# mapleCUx_med_018.net
KiCad netlist of a schematic drawn in EAGLE
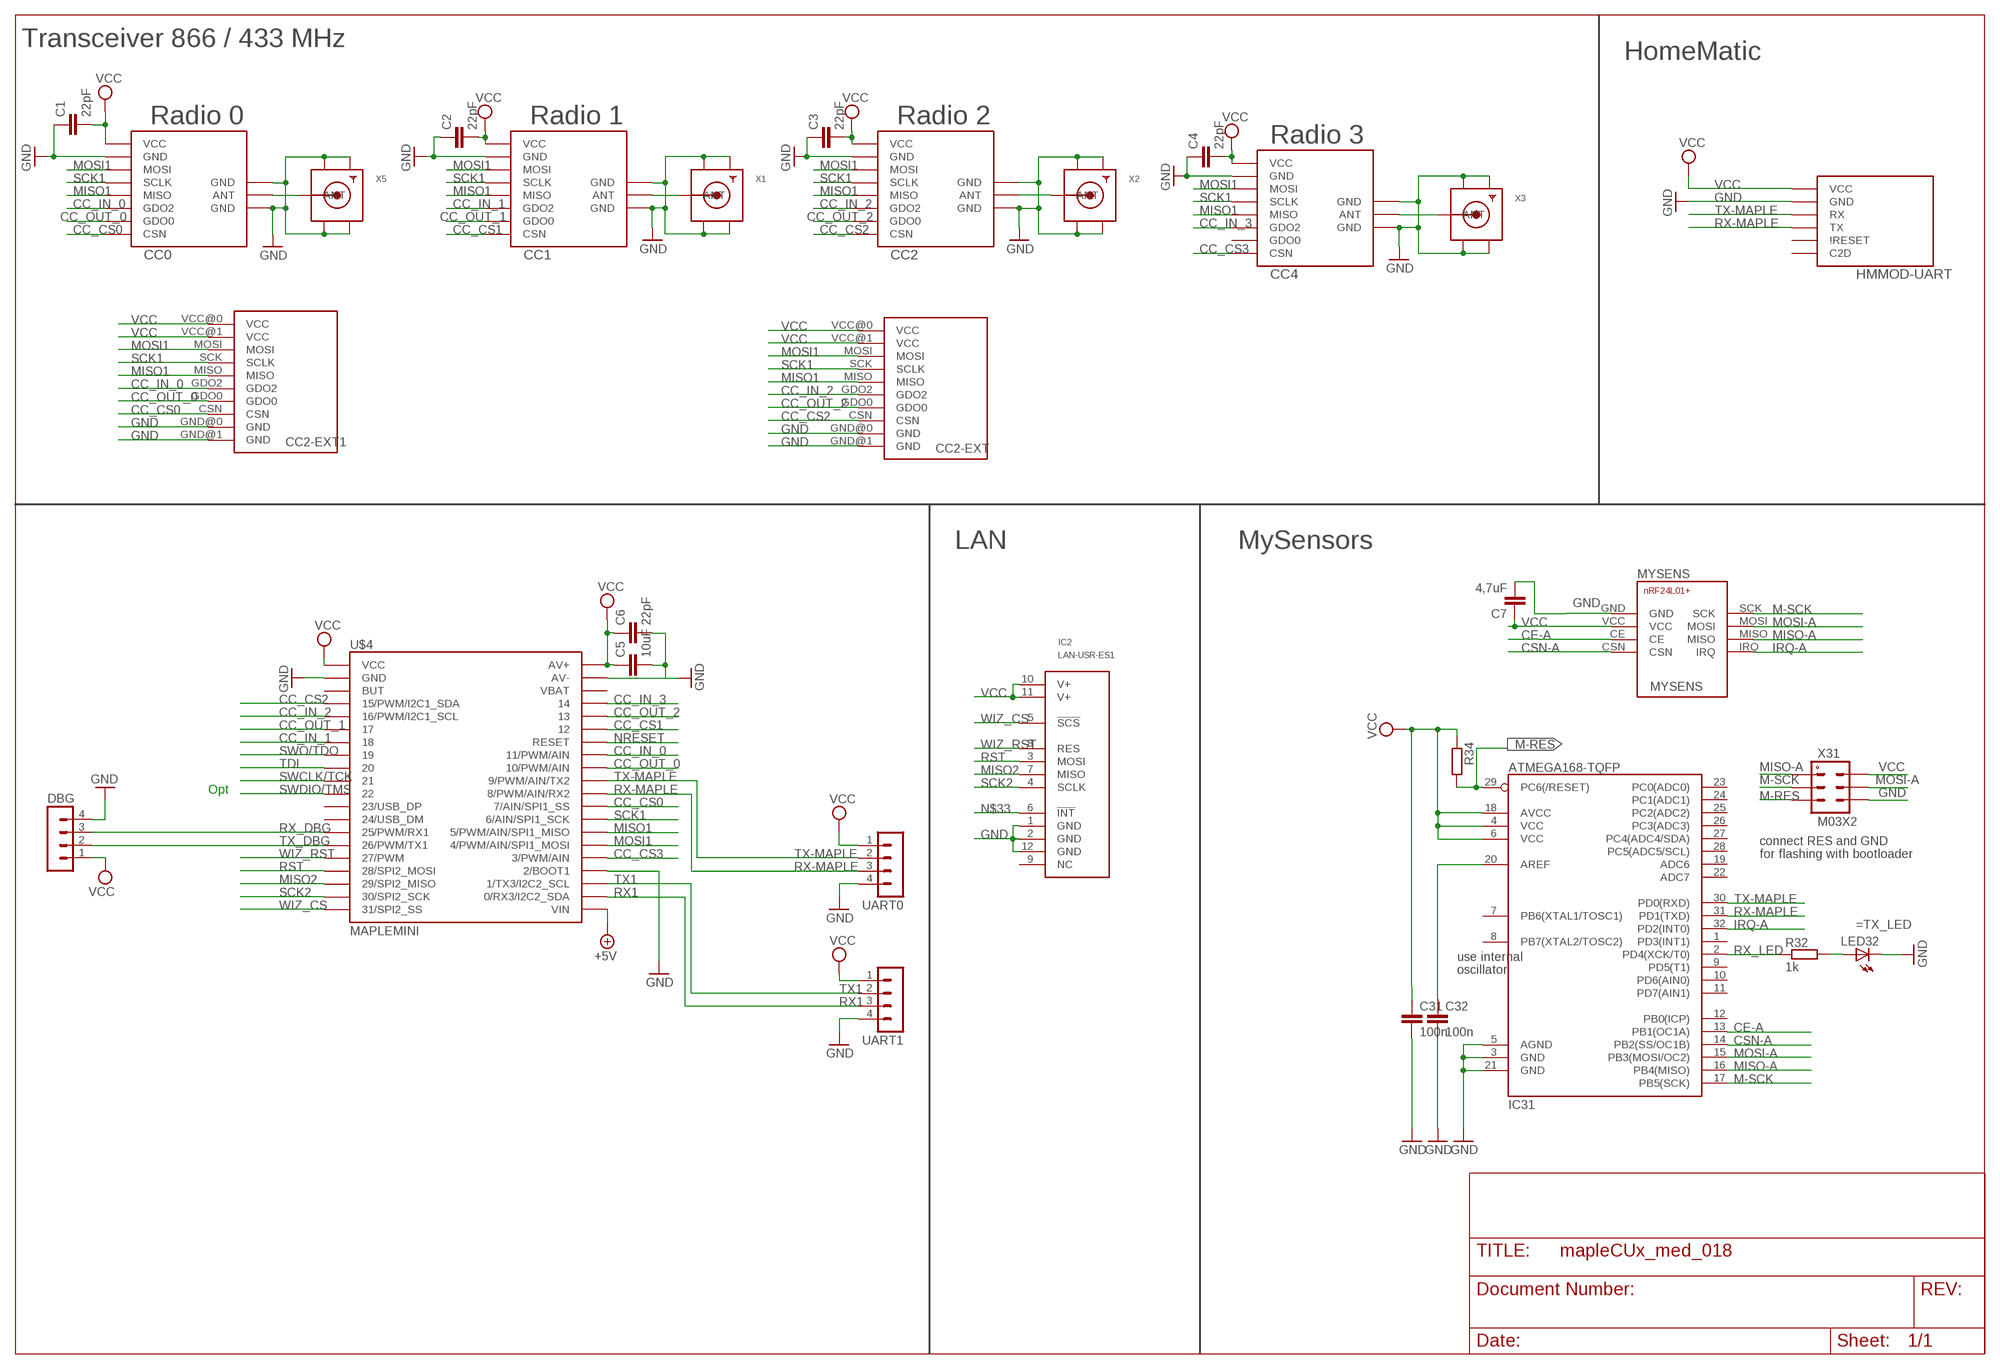
[diagram p0: schematic, sheet 1]

(export (version "E")
  (design (tool "Eeschema 10.0.6"))
  (components
    (comp (ref "C1")
      (value "22pF")
      (footprint "eagle-import:C0805")
      (libsource (lib "eagle-import") (part "C-EUC0805"))
    )
    (comp (ref "C2")
      (value "22pF")
      (footprint "eagle-import:C0805")
      (libsource (lib "eagle-import") (part "C-EUC0805"))
    )
    (comp (ref "C3")
      (value "22pF")
      (footprint "eagle-import:C0805")
      (libsource (lib "eagle-import") (part "C-EUC0805"))
    )
    (comp (ref "C4")
      (value "22pF")
      (footprint "eagle-import:C0805")
      (libsource (lib "eagle-import") (part "C-EUC0805"))
    )
    (comp (ref "C5")
      (value "10uF")
      (footprint "eagle-import:C1210")
      (libsource (lib "eagle-import") (part "C-EUC1210"))
    )
    (comp (ref "C6")
      (value "22pF")
      (footprint "eagle-import:C0805")
      (libsource (lib "eagle-import") (part "C-EUC0805"))
    )
    (comp (ref "C7")
      (value "4,7uF")
      (footprint "eagle-import:C1210")
      (libsource (lib "eagle-import") (part "C-EUC1210"))
    )
    (comp (ref "C31")
      (value "100n")
      (footprint "eagle-import:C0805")
      (libsource (lib "eagle-import") (part "C-EUC0805"))
    )
    (comp (ref "C32")
      (value "100n")
      (footprint "eagle-import:C0805")
      (libsource (lib "eagle-import") (part "C-EUC0805"))
    )
    (comp (ref "CC0")
      (value "CC1101")
      (footprint "eagle-import:CC1101_MODULE1_SMD")
      (libsource (lib "eagle-import") (part "CC1101_MODULE1SMD"))
    )
    (comp (ref "CC1")
      (value "CC1101_MODULE1SMD")
      (footprint "eagle-import:CC1101_MODULE1_SMD")
      (libsource (lib "eagle-import") (part "CC1101_MODULE1SMD"))
    )
    (comp (ref "CC2")
      (value "CC1101_MODULE1SMD")
      (footprint "eagle-import:CC1101_MODULE1_SMD")
      (libsource (lib "eagle-import") (part "CC1101_MODULE1SMD"))
    )
    (comp (ref "CC2-EXT")
      (value "CC1101_MODULE3_DIL")
      (footprint "eagle-import:CC1101_MODULE3_DIL")
      (libsource (lib "eagle-import") (part "CC1101_MODULE3_DIL"))
    )
    (comp (ref "CC2-EXT1")
      (value "CC1101_MODULE3_DIL")
      (footprint "eagle-import:CC1101_MODULE3_DIL")
      (libsource (lib "eagle-import") (part "CC1101_MODULE3_DIL"))
    )
    (comp (ref "CC4")
      (value "CC1101_MODULE1SMD")
      (footprint "eagle-import:CC1101_MODULE1_SMD")
      (libsource (lib "eagle-import") (part "CC1101_MODULE1SMD"))
    )
    (comp (ref "DBG")
      (value "MA04-1")
      (footprint "eagle-import:MA04-1")
      (libsource (lib "eagle-import") (part "MA04-1"))
    )
    (comp (ref "HMMOD-UART")
      (value "HM-MOD-UARTDIL")
      (footprint "eagle-import:HM-MOD-UART-DIL")
      (libsource (lib "eagle-import") (part "HM-MOD-UARTDIL"))
    )
    (comp (ref "IC2")
      (value "LAN-USR-ES1")
      (footprint "eagle-import:USR-ES1")
      (libsource (lib "eagle-import") (part "LAN-USR-ES1"))
    )
    (comp (ref "IC31")
      (value "ATMEGA168-TQFP")
      (footprint "eagle-import:TQFP32-08")
      (libsource (lib "eagle-import") (part "ATMEGA168-TQFP"))
    )
    (comp (ref "LED32")
      (value "LEDCHIPLED_0805")
      (footprint "eagle-import:CHIPLED_0805")
      (libsource (lib "eagle-import") (part "LEDCHIPLED_0805"))
    )
    (comp (ref "MYSENS")
      (value "NRF24L01+SMD")
      (footprint "eagle-import:NRF24L01+SMD")
      (libsource (lib "eagle-import") (part "NRF24L01+SMD"))
    )
    (comp (ref "R32")
      (value "1k")
      (footprint "eagle-import:R0805")
      (libsource (lib "eagle-import") (part "R-EU_R0805"))
    )
    (comp (ref "R34")
      (value "R-EU_R0805")
      (footprint "eagle-import:R0805")
      (libsource (lib "eagle-import") (part "R-EU_R0805"))
    )
    (comp (ref "U$4")
      (value "MAPLEMINI")
      (footprint "eagle-import:20-DIP")
      (libsource (lib "eagle-import") (part "MAPLEMINI"))
    )
    (comp (ref "UART0")
      (value "MA04-1")
      (footprint "eagle-import:MA04-1")
      (libsource (lib "eagle-import") (part "MA04-1"))
    )
    (comp (ref "UART1")
      (value "MA04-1")
      (footprint "eagle-import:MA04-1")
      (libsource (lib "eagle-import") (part "MA04-1"))
    )
    (comp (ref "X1")
      (value "SMACONNECTOR_EDGE_UFL")
      (footprint "eagle-import:SMA_EDGELAUNCH_UFL")
      (libsource (lib "eagle-import") (part "SMACONNECTOR_EDGE_UFL"))
    )
    (comp (ref "X2")
      (value "SMACONNECTOR_EDGE_UFL")
      (footprint "eagle-import:SMA_EDGELAUNCH_UFL")
      (libsource (lib "eagle-import") (part "SMACONNECTOR_EDGE_UFL"))
    )
    (comp (ref "X3")
      (value "SMACONNECTOR_EDGE_UFL")
      (footprint "eagle-import:SMA_EDGELAUNCH_UFL")
      (libsource (lib "eagle-import") (part "SMACONNECTOR_EDGE_UFL"))
    )
    (comp (ref "X5")
      (value "SMACONNECTOR_EDGE_UFL")
      (footprint "eagle-import:SMA_EDGELAUNCH_UFL")
      (libsource (lib "eagle-import") (part "SMACONNECTOR_EDGE_UFL"))
    )
    (comp (ref "X31")
      (value "M03X2")
      (footprint "eagle-import:2X03-1.27MM_SMD")
      (libsource (lib "eagle-import") (part "M03X2"))
    )
  )
  (nets
    (net (code "1") (name "+5V") (class "Default")
      (node (ref "U$4") (pin "21") (pinfunction "VIN_21") (pintype "bidirectional"))
    )
    (net (code "2") (name "/CC_CS0") (class "Default")
      (node (ref "CC0") (pin "CSN") (pinfunction "CSN_CSN") (pintype "bidirectional"))
      (node (ref "CC2-EXT1") (pin "CSN") (pinfunction "CSN_CSN") (pintype "bidirectional"))
      (node (ref "U$4") (pin "29") (pinfunction "7/AIN/SPI1_SS_29") (pintype "bidirectional"))
    )
    (net (code "3") (name "/CC_CS1") (class "Default")
      (node (ref "CC1") (pin "CSN") (pinfunction "CSN_CSN") (pintype "bidirectional"))
      (node (ref "U$4") (pin "35") (pinfunction "12_35") (pintype "bidirectional"))
    )
    (net (code "4") (name "/CC_CS2") (class "Default")
      (node (ref "CC2") (pin "CSN") (pinfunction "CSN_CSN") (pintype "bidirectional"))
      (node (ref "CC2-EXT") (pin "CSN") (pinfunction "CSN_CSN") (pintype "bidirectional"))
      (node (ref "U$4") (pin "4") (pinfunction "15/PWM/I2C1_SDA_4") (pintype "bidirectional"))
    )
    (net (code "5") (name "/CC_CS3") (class "Default")
      (node (ref "CC4") (pin "CSN") (pinfunction "CSN_CSN") (pintype "bidirectional"))
      (node (ref "U$4") (pin "25") (pinfunction "3/PWM/AIN_25") (pintype "bidirectional"))
    )
    (net (code "6") (name "/CC_IN_0") (class "Default")
      (node (ref "CC0") (pin "GDO2") (pinfunction "GDO2_GDO2") (pintype "bidirectional"))
      (node (ref "CC2-EXT1") (pin "GDO2") (pinfunction "GDO2_GDO2") (pintype "bidirectional"))
      (node (ref "U$4") (pin "33") (pinfunction "11/PWM/AIN_33") (pintype "bidirectional"))
    )
    (net (code "7") (name "/CC_IN_1") (class "Default")
      (node (ref "CC1") (pin "GDO2") (pinfunction "GDO2_GDO2") (pintype "bidirectional"))
      (node (ref "U$4") (pin "7") (pinfunction "18_7") (pintype "bidirectional"))
    )
    (net (code "8") (name "/CC_IN_2") (class "Default")
      (node (ref "CC2") (pin "GDO2") (pinfunction "GDO2_GDO2") (pintype "bidirectional"))
      (node (ref "CC2-EXT") (pin "GDO2") (pinfunction "GDO2_GDO2") (pintype "bidirectional"))
      (node (ref "U$4") (pin "5") (pinfunction "16/PWM/I2C1_SCL_5") (pintype "bidirectional"))
    )
    (net (code "9") (name "/CC_IN_3") (class "Default")
      (node (ref "CC4") (pin "GDO2") (pinfunction "GDO2_GDO2") (pintype "bidirectional"))
      (node (ref "U$4") (pin "37") (pinfunction "14_37") (pintype "bidirectional"))
    )
    (net (code "10") (name "/CC_OUT_0") (class "Default")
      (node (ref "CC0") (pin "GDO0") (pinfunction "GDO0_GDO0") (pintype "bidirectional"))
      (node (ref "CC2-EXT1") (pin "GDO0") (pinfunction "GDO0_GDO0") (pintype "bidirectional"))
      (node (ref "U$4") (pin "32") (pinfunction "10/PWM/AIN_32") (pintype "bidirectional"))
    )
    (net (code "11") (name "/CC_OUT_1") (class "Default")
      (node (ref "CC1") (pin "GDO0") (pinfunction "GDO0_GDO0") (pintype "bidirectional"))
      (node (ref "U$4") (pin "6") (pinfunction "17_6") (pintype "bidirectional"))
    )
    (net (code "12") (name "/CC_OUT_2") (class "Default")
      (node (ref "CC2") (pin "GDO0") (pinfunction "GDO0_GDO0") (pintype "bidirectional"))
      (node (ref "CC2-EXT") (pin "GDO0") (pinfunction "GDO0_GDO0") (pintype "bidirectional"))
      (node (ref "U$4") (pin "36") (pinfunction "13_36") (pintype "bidirectional"))
    )
    (net (code "13") (name "/CE-A") (class "Default")
      (node (ref "IC31") (pin "13") (pinfunction "PB1(OC1A)_13") (pintype "bidirectional"))
      (node (ref "MYSENS") (pin "CE") (pinfunction "CE_CE") (pintype "bidirectional"))
    )
    (net (code "14") (name "/CSN-A") (class "Default")
      (node (ref "IC31") (pin "14") (pinfunction "PB2(SS/OC1B)_14") (pintype "bidirectional"))
      (node (ref "MYSENS") (pin "CSN") (pinfunction "CSN_CSN") (pintype "bidirectional"))
    )
    (net (code "15") (name "/IRQ-A") (class "Default")
      (node (ref "IC31") (pin "32") (pinfunction "PD2(INT0)_32") (pintype "bidirectional"))
      (node (ref "MYSENS") (pin "IRQ") (pinfunction "IRQ_IRQ") (pintype "bidirectional"))
    )
    (net (code "16") (name "/M-RES") (class "Default")
      (node (ref "IC31") (pin "29") (pinfunction "PC6(/RESET)_29") (pintype "bidirectional"))
      (node (ref "R34") (pin "2") (pinfunction "2_2") (pintype "passive"))
      (node (ref "X31") (pin "P$5") (pinfunction "5_P$5") (pintype "passive"))
    )
    (net (code "17") (name "/M-SCK") (class "Default")
      (node (ref "IC31") (pin "17") (pinfunction "PB5(SCK)_17") (pintype "bidirectional"))
      (node (ref "MYSENS") (pin "SCK") (pinfunction "SCK_SCK") (pintype "bidirectional"))
      (node (ref "X31") (pin "P$3") (pinfunction "3_P$3") (pintype "passive"))
    )
    (net (code "18") (name "/MISO-A") (class "Default")
      (node (ref "IC31") (pin "16") (pinfunction "PB4(MISO)_16") (pintype "bidirectional"))
      (node (ref "MYSENS") (pin "MISO") (pinfunction "MISO_MISO") (pintype "bidirectional"))
      (node (ref "X31") (pin "P$1") (pinfunction "1_P$1") (pintype "passive"))
    )
    (net (code "19") (name "/MISO1") (class "Default")
      (node (ref "CC0") (pin "MISO") (pinfunction "MISO_MISO") (pintype "bidirectional"))
      (node (ref "CC1") (pin "MISO") (pinfunction "MISO_MISO") (pintype "bidirectional"))
      (node (ref "CC2") (pin "MISO") (pinfunction "MISO_MISO") (pintype "bidirectional"))
      (node (ref "CC2-EXT") (pin "MISO") (pinfunction "MISO_MISO") (pintype "bidirectional"))
      (node (ref "CC2-EXT1") (pin "MISO") (pinfunction "MISO_MISO") (pintype "bidirectional"))
      (node (ref "CC4") (pin "MISO") (pinfunction "MISO_MISO") (pintype "bidirectional"))
      (node (ref "U$4") (pin "27") (pinfunction "5/PWM/AIN/SPI1_MISO_27") (pintype "bidirectional"))
    )
    (net (code "20") (name "/MISO2") (class "Default")
      (node (ref "IC2") (pin "7") (pinfunction "MISO_7") (pintype "bidirectional"))
      (node (ref "U$4") (pin "18") (pinfunction "29/SPI2_MISO_18") (pintype "bidirectional"))
    )
    (net (code "21") (name "/MOSI-A") (class "Default")
      (node (ref "IC31") (pin "15") (pinfunction "PB3(MOSI/OC2)_15") (pintype "bidirectional"))
      (node (ref "MYSENS") (pin "MOSI") (pinfunction "MOSI_MOSI") (pintype "bidirectional"))
      (node (ref "X31") (pin "P$4") (pinfunction "4_P$4") (pintype "passive"))
    )
    (net (code "22") (name "/MOSI1") (class "Default")
      (node (ref "CC0") (pin "MOSI") (pinfunction "MOSI_MOSI") (pintype "bidirectional"))
      (node (ref "CC1") (pin "MOSI") (pinfunction "MOSI_MOSI") (pintype "bidirectional"))
      (node (ref "CC2") (pin "MOSI") (pinfunction "MOSI_MOSI") (pintype "bidirectional"))
      (node (ref "CC2-EXT") (pin "MOSI") (pinfunction "MOSI_MOSI") (pintype "bidirectional"))
      (node (ref "CC2-EXT1") (pin "MOSI") (pinfunction "MOSI_MOSI") (pintype "bidirectional"))
      (node (ref "CC4") (pin "MOSI") (pinfunction "MOSI_MOSI") (pintype "bidirectional"))
      (node (ref "U$4") (pin "26") (pinfunction "4/PWM/AIN/SPI1_MOSI_26") (pintype "bidirectional"))
    )
    (net (code "23") (name "/N$33") (class "Default")
      (node (ref "IC2") (pin "6") (pinfunction "~{INT}_6") (pintype "output"))
    )
    (net (code "24") (name "/NRESET") (class "Default")
      (node (ref "U$4") (pin "34") (pinfunction "RESET_34") (pintype "bidirectional"))
    )
    (net (code "25") (name "/RST") (class "Default")
      (node (ref "IC2") (pin "3") (pinfunction "MOSI_3") (pintype "bidirectional"))
      (node (ref "U$4") (pin "17") (pinfunction "28/SPI2_MOSI_17") (pintype "bidirectional"))
    )
    (net (code "26") (name "/RX-MAPLE") (class "Default")
      (node (ref "HMMOD-UART") (pin "5") (pinfunction "TX_5") (pintype "bidirectional"))
      (node (ref "IC31") (pin "31") (pinfunction "PD1(TXD)_31") (pintype "bidirectional"))
      (node (ref "U$4") (pin "30") (pinfunction "8/PWM/AIN/RX2_30") (pintype "bidirectional"))
      (node (ref "UART0") (pin "3") (pinfunction "3_3") (pintype "passive"))
    )
    (net (code "27") (name "/RX1") (class "Default")
      (node (ref "U$4") (pin "22") (pinfunction "0/RX3/I2C2_SDA_22") (pintype "bidirectional"))
      (node (ref "UART1") (pin "3") (pinfunction "3_3") (pintype "passive"))
    )
    (net (code "28") (name "/RX_DBG") (class "Default")
      (node (ref "DBG") (pin "3") (pinfunction "3_3") (pintype "passive"))
      (node (ref "U$4") (pin "14") (pinfunction "25/PWM/RX1_14") (pintype "bidirectional"))
    )
    (net (code "29") (name "/RX_LED") (class "Default")
      (node (ref "IC31") (pin "2") (pinfunction "PD4(XCK/T0)_2") (pintype "bidirectional"))
      (node (ref "R32") (pin "1") (pinfunction "1_1") (pintype "passive"))
    )
    (net (code "30") (name "/SCK1") (class "Default")
      (node (ref "CC0") (pin "SCLK") (pinfunction "SCLK_SCLK") (pintype "bidirectional"))
      (node (ref "CC1") (pin "SCLK") (pinfunction "SCLK_SCLK") (pintype "bidirectional"))
      (node (ref "CC2") (pin "SCLK") (pinfunction "SCLK_SCLK") (pintype "bidirectional"))
      (node (ref "CC2-EXT") (pin "SCK") (pinfunction "SCLK_SCK") (pintype "bidirectional"))
      (node (ref "CC2-EXT1") (pin "SCK") (pinfunction "SCLK_SCK") (pintype "bidirectional"))
      (node (ref "CC4") (pin "SCLK") (pinfunction "SCLK_SCLK") (pintype "bidirectional"))
      (node (ref "U$4") (pin "28") (pinfunction "6/AIN/SPI1_SCK_28") (pintype "bidirectional"))
    )
    (net (code "31") (name "/SCK2") (class "Default")
      (node (ref "IC2") (pin "4") (pinfunction "SCLK_4") (pintype "input"))
      (node (ref "U$4") (pin "19") (pinfunction "30/SPI2_SCK_19") (pintype "bidirectional"))
    )
    (net (code "32") (name "/SWCLK{slash}TCK") (class "Default")
      (node (ref "U$4") (pin "10") (pinfunction "21_10") (pintype "bidirectional"))
    )
    (net (code "33") (name "/SWDIO{slash}TMS") (class "Default")
      (node (ref "U$4") (pin "11") (pinfunction "22_11") (pintype "bidirectional"))
    )
    (net (code "34") (name "/SWO{slash}TDO") (class "Default")
      (node (ref "U$4") (pin "8") (pinfunction "19_8") (pintype "bidirectional"))
    )
    (net (code "35") (name "/TDI") (class "Default")
      (node (ref "U$4") (pin "9") (pinfunction "20_9") (pintype "bidirectional"))
    )
    (net (code "36") (name "/TX-MAPLE") (class "Default")
      (node (ref "HMMOD-UART") (pin "6") (pinfunction "RX_6") (pintype "bidirectional"))
      (node (ref "IC31") (pin "30") (pinfunction "PD0(RXD)_30") (pintype "bidirectional"))
      (node (ref "U$4") (pin "31") (pinfunction "9/PWM/AIN/TX2_31") (pintype "bidirectional"))
      (node (ref "UART0") (pin "2") (pinfunction "2_2") (pintype "passive"))
    )
    (net (code "37") (name "/TX1") (class "Default")
      (node (ref "U$4") (pin "23") (pinfunction "1/TX3/I2C2_SCL_23") (pintype "bidirectional"))
      (node (ref "UART1") (pin "2") (pinfunction "2_2") (pintype "passive"))
    )
    (net (code "38") (name "/TX_DBG") (class "Default")
      (node (ref "DBG") (pin "2") (pinfunction "2_2") (pintype "passive"))
      (node (ref "U$4") (pin "15") (pinfunction "26/PWM/TX1_15") (pintype "bidirectional"))
    )
    (net (code "39") (name "/WIZ_CS") (class "Default")
      (node (ref "IC2") (pin "5") (pinfunction "~{SCS}_5") (pintype "input"))
      (node (ref "U$4") (pin "20") (pinfunction "31/SPI2_SS_20") (pintype "bidirectional"))
    )
    (net (code "40") (name "/WIZ_RST") (class "Default")
      (node (ref "IC2") (pin "8") (pinfunction "RES_8") (pintype "input"))
      (node (ref "U$4") (pin "16") (pinfunction "27/PWM_16") (pintype "bidirectional"))
    )
    (net (code "41") (name "GND") (class "Default")
      (node (ref "C1") (pin "1") (pinfunction "1_1") (pintype "passive"))
      (node (ref "C2") (pin "1") (pinfunction "1_1") (pintype "passive"))
      (node (ref "C3") (pin "1") (pinfunction "1_1") (pintype "passive"))
      (node (ref "C31") (pin "2") (pinfunction "2_2") (pintype "passive"))
      (node (ref "C32") (pin "2") (pinfunction "2_2") (pintype "passive"))
      (node (ref "C4") (pin "1") (pinfunction "1_1") (pintype "passive"))
      (node (ref "C5") (pin "2") (pinfunction "2_2") (pintype "passive"))
      (node (ref "C6") (pin "2") (pinfunction "2_2") (pintype "passive"))
      (node (ref "C7") (pin "2") (pinfunction "2_2") (pintype "passive"))
      (node (ref "CC0") (pin "GND@0") (pinfunction "GND_GND@0") (pintype "power_in"))
      (node (ref "CC0") (pin "GND@1") (pinfunction "GND_GND@1") (pintype "power_in"))
      (node (ref "CC0") (pin "GND@2") (pinfunction "GND_GND@2") (pintype "power_in"))
      (node (ref "CC1") (pin "GND@0") (pinfunction "GND_GND@0") (pintype "power_in"))
      (node (ref "CC1") (pin "GND@1") (pinfunction "GND_GND@1") (pintype "power_in"))
      (node (ref "CC1") (pin "GND@2") (pinfunction "GND_GND@2") (pintype "power_in"))
      (node (ref "CC2") (pin "GND@0") (pinfunction "GND_GND@0") (pintype "power_in"))
      (node (ref "CC2") (pin "GND@1") (pinfunction "GND_GND@1") (pintype "power_in"))
      (node (ref "CC2") (pin "GND@2") (pinfunction "GND_GND@2") (pintype "power_in"))
      (node (ref "CC2-EXT") (pin "GND@0") (pinfunction "GND_GND@0") (pintype "power_in"))
      (node (ref "CC2-EXT") (pin "GND@1") (pinfunction "GND_GND@1") (pintype "power_in"))
      (node (ref "CC2-EXT1") (pin "GND@0") (pinfunction "GND_GND@0") (pintype "power_in"))
      (node (ref "CC2-EXT1") (pin "GND@1") (pinfunction "GND_GND@1") (pintype "power_in"))
      (node (ref "CC4") (pin "GND@0") (pinfunction "GND_GND@0") (pintype "power_in"))
      (node (ref "CC4") (pin "GND@1") (pinfunction "GND_GND@1") (pintype "power_in"))
      (node (ref "CC4") (pin "GND@2") (pinfunction "GND_GND@2") (pintype "power_in"))
      (node (ref "DBG") (pin "4") (pinfunction "4_4") (pintype "passive"))
      (node (ref "HMMOD-UART") (pin "2") (pinfunction "GND_2") (pintype "power_in"))
      (node (ref "IC2") (pin "1") (pinfunction "GND_1") (pintype "power_in"))
      (node (ref "IC2") (pin "12") (pinfunction "GND_12") (pintype "power_in"))
      (node (ref "IC2") (pin "2") (pinfunction "GND_2") (pintype "power_in"))
      (node (ref "IC31") (pin "21") (pinfunction "GND_21") (pintype "bidirectional"))
      (node (ref "IC31") (pin "3") (pinfunction "GND_3") (pintype "bidirectional"))
      (node (ref "IC31") (pin "5") (pinfunction "AGND_5") (pintype "bidirectional"))
      (node (ref "LED32") (pin "C") (pinfunction "C_C") (pintype "passive"))
      (node (ref "MYSENS") (pin "GND") (pinfunction "GND_GND") (pintype "power_in"))
      (node (ref "U$4") (pin "2") (pinfunction "GND_2") (pintype "bidirectional"))
      (node (ref "U$4") (pin "24") (pinfunction "2/BOOT1_24") (pintype "bidirectional"))
      (node (ref "U$4") (pin "39") (pinfunction "AV-_39") (pintype "bidirectional"))
      (node (ref "UART0") (pin "4") (pinfunction "4_4") (pintype "passive"))
      (node (ref "UART1") (pin "4") (pinfunction "4_4") (pintype "passive"))
      (node (ref "X1") (pin "GND@1") (pinfunction "GND1_GND@1") (pintype "power_in"))
      (node (ref "X1") (pin "GND@2") (pinfunction "GND2_GND@2") (pintype "power_in"))
      (node (ref "X1") (pin "GND@3") (pinfunction "GND3_GND@3") (pintype "power_in"))
      (node (ref "X1") (pin "GND@4") (pinfunction "GND4_GND@4") (pintype "power_in"))
      (node (ref "X2") (pin "GND@1") (pinfunction "GND1_GND@1") (pintype "power_in"))
      (node (ref "X2") (pin "GND@2") (pinfunction "GND2_GND@2") (pintype "power_in"))
      (node (ref "X2") (pin "GND@3") (pinfunction "GND3_GND@3") (pintype "power_in"))
      (node (ref "X2") (pin "GND@4") (pinfunction "GND4_GND@4") (pintype "power_in"))
      (node (ref "X3") (pin "GND@1") (pinfunction "GND1_GND@1") (pintype "power_in"))
      (node (ref "X3") (pin "GND@2") (pinfunction "GND2_GND@2") (pintype "power_in"))
      (node (ref "X3") (pin "GND@3") (pinfunction "GND3_GND@3") (pintype "power_in"))
      (node (ref "X3") (pin "GND@4") (pinfunction "GND4_GND@4") (pintype "power_in"))
      (node (ref "X31") (pin "P$6") (pinfunction "6_P$6") (pintype "passive"))
      (node (ref "X5") (pin "GND@1") (pinfunction "GND1_GND@1") (pintype "power_in"))
      (node (ref "X5") (pin "GND@2") (pinfunction "GND2_GND@2") (pintype "power_in"))
      (node (ref "X5") (pin "GND@3") (pinfunction "GND3_GND@3") (pintype "power_in"))
      (node (ref "X5") (pin "GND@4") (pinfunction "GND4_GND@4") (pintype "power_in"))
    )
    (net (code "42") (name "Net-(IC31-AREF)") (class "Default")
      (node (ref "C32") (pin "1") (pinfunction "1_1") (pintype "passive"))
      (node (ref "IC31") (pin "20") (pinfunction "AREF_20") (pintype "bidirectional"))
    )
    (net (code "43") (name "Net-(LED32-PadA)") (class "Default")
      (node (ref "LED32") (pin "A") (pinfunction "A_A") (pintype "passive"))
      (node (ref "R32") (pin "2") (pinfunction "2_2") (pintype "passive"))
    )
    (net (code "44") (name "Net-(X1-ANT)") (class "Default")
      (node (ref "CC1") (pin "ANT") (pinfunction "ANT_ANT") (pintype "output"))
      (node (ref "X1") (pin "P") (pinfunction "ANT_P") (pintype "bidirectional"))
    )
    (net (code "45") (name "Net-(X2-ANT)") (class "Default")
      (node (ref "CC2") (pin "ANT") (pinfunction "ANT_ANT") (pintype "output"))
      (node (ref "X2") (pin "P") (pinfunction "ANT_P") (pintype "bidirectional"))
    )
    (net (code "46") (name "Net-(X3-ANT)") (class "Default")
      (node (ref "CC4") (pin "ANT") (pinfunction "ANT_ANT") (pintype "output"))
      (node (ref "X3") (pin "P") (pinfunction "ANT_P") (pintype "bidirectional"))
    )
    (net (code "47") (name "Net-(X5-ANT)") (class "Default")
      (node (ref "CC0") (pin "ANT") (pinfunction "ANT_ANT") (pintype "output"))
      (node (ref "X5") (pin "P") (pinfunction "ANT_P") (pintype "bidirectional"))
    )
    (net (code "48") (name "VCC") (class "Default")
      (node (ref "C1") (pin "2") (pinfunction "2_2") (pintype "passive"))
      (node (ref "C2") (pin "2") (pinfunction "2_2") (pintype "passive"))
      (node (ref "C3") (pin "2") (pinfunction "2_2") (pintype "passive"))
      (node (ref "C31") (pin "1") (pinfunction "1_1") (pintype "passive"))
      (node (ref "C4") (pin "2") (pinfunction "2_2") (pintype "passive"))
      (node (ref "C5") (pin "1") (pinfunction "1_1") (pintype "passive"))
      (node (ref "C6") (pin "1") (pinfunction "1_1") (pintype "passive"))
      (node (ref "C7") (pin "1") (pinfunction "1_1") (pintype "passive"))
      (node (ref "CC0") (pin "VCC") (pinfunction "VCC_VCC") (pintype "power_in"))
      (node (ref "CC1") (pin "VCC") (pinfunction "VCC_VCC") (pintype "power_in"))
      (node (ref "CC2") (pin "VCC") (pinfunction "VCC_VCC") (pintype "power_in"))
      (node (ref "CC2-EXT") (pin "VCC@0") (pinfunction "VCC_VCC@0") (pintype "power_in"))
      (node (ref "CC2-EXT") (pin "VCC@1") (pinfunction "VCC_VCC@1") (pintype "power_in"))
      (node (ref "CC2-EXT1") (pin "VCC@0") (pinfunction "VCC_VCC@0") (pintype "power_in"))
      (node (ref "CC2-EXT1") (pin "VCC@1") (pinfunction "VCC_VCC@1") (pintype "power_in"))
      (node (ref "CC4") (pin "VCC") (pinfunction "VCC_VCC") (pintype "power_in"))
      (node (ref "DBG") (pin "1") (pinfunction "1_1") (pintype "passive"))
      (node (ref "HMMOD-UART") (pin "1") (pinfunction "VCC_1") (pintype "power_in"))
      (node (ref "IC2") (pin "10") (pinfunction "V+_10") (pintype "power_in"))
      (node (ref "IC2") (pin "11") (pinfunction "V+_11") (pintype "power_in"))
      (node (ref "IC31") (pin "18") (pinfunction "AVCC_18") (pintype "bidirectional"))
      (node (ref "IC31") (pin "4") (pinfunction "VCC_4") (pintype "bidirectional"))
      (node (ref "IC31") (pin "6") (pinfunction "VCC_6") (pintype "bidirectional"))
      (node (ref "MYSENS") (pin "VCC") (pinfunction "VCC_VCC") (pintype "power_in"))
      (node (ref "R34") (pin "1") (pinfunction "1_1") (pintype "passive"))
      (node (ref "U$4") (pin "1") (pinfunction "VCC_1") (pintype "bidirectional"))
      (node (ref "U$4") (pin "40") (pinfunction "AV+_40") (pintype "bidirectional"))
      (node (ref "UART0") (pin "1") (pinfunction "1_1") (pintype "passive"))
      (node (ref "UART1") (pin "1") (pinfunction "1_1") (pintype "passive"))
      (node (ref "X31") (pin "P$2") (pinfunction "2_P$2") (pintype "passive"))
    )
    (net (code "49") (name "unconnected-(CC4-PadGDO0)") (class "Default")
      (node (ref "CC4") (pin "GDO0") (pinfunction "GDO0_GDO0") (pintype "bidirectional"))
    )
    (net (code "50") (name "unconnected-(HMMOD-UART-C2D-Pad3)") (class "Default")
      (node (ref "HMMOD-UART") (pin "3") (pinfunction "C2D_3") (pintype "bidirectional"))
    )
    (net (code "51") (name "unconnected-(HMMOD-UART-\\~{RESET}-Pad4)") (class "Default")
      (node (ref "HMMOD-UART") (pin "4") (pinfunction "\\~{RESET}_4") (pintype "bidirectional"))
    )
    (net (code "52") (name "unconnected-(IC2-NC-Pad9)") (class "Default")
      (node (ref "IC2") (pin "9") (pinfunction "NC_9") (pintype "no_connect"))
    )
    (net (code "53") (name "unconnected-(IC31-ADC6-Pad19)") (class "Default")
      (node (ref "IC31") (pin "19") (pinfunction "ADC6_19") (pintype "bidirectional"))
    )
    (net (code "54") (name "unconnected-(IC31-ADC7-Pad22)") (class "Default")
      (node (ref "IC31") (pin "22") (pinfunction "ADC7_22") (pintype "bidirectional"))
    )
    (net (code "55") (name "unconnected-(IC31-PB0(ICP)-Pad12)") (class "Default")
      (node (ref "IC31") (pin "12") (pinfunction "PB0(ICP)_12") (pintype "bidirectional"))
    )
    (net (code "56") (name "unconnected-(IC31-PB6(XTAL1{slash}TOSC1)-Pad7)") (class "Default")
      (node (ref "IC31") (pin "7") (pinfunction "PB6(XTAL1/TOSC1)_7") (pintype "bidirectional"))
    )
    (net (code "57") (name "unconnected-(IC31-PB7(XTAL2{slash}TOSC2)-Pad8)") (class "Default")
      (node (ref "IC31") (pin "8") (pinfunction "PB7(XTAL2/TOSC2)_8") (pintype "bidirectional"))
    )
    (net (code "58") (name "unconnected-(IC31-PC0(ADC0)-Pad23)") (class "Default")
      (node (ref "IC31") (pin "23") (pinfunction "PC0(ADC0)_23") (pintype "bidirectional"))
    )
    (net (code "59") (name "unconnected-(IC31-PC1(ADC1)-Pad24)") (class "Default")
      (node (ref "IC31") (pin "24") (pinfunction "PC1(ADC1)_24") (pintype "bidirectional"))
    )
    (net (code "60") (name "unconnected-(IC31-PC2(ADC2)-Pad25)") (class "Default")
      (node (ref "IC31") (pin "25") (pinfunction "PC2(ADC2)_25") (pintype "bidirectional"))
    )
    (net (code "61") (name "unconnected-(IC31-PC3(ADC3)-Pad26)") (class "Default")
      (node (ref "IC31") (pin "26") (pinfunction "PC3(ADC3)_26") (pintype "bidirectional"))
    )
    (net (code "62") (name "unconnected-(IC31-PC4(ADC4{slash}SDA)-Pad27)") (class "Default")
      (node (ref "IC31") (pin "27") (pinfunction "PC4(ADC4/SDA)_27") (pintype "bidirectional"))
    )
    (net (code "63") (name "unconnected-(IC31-PC5(ADC5{slash}SCL)-Pad28)") (class "Default")
      (node (ref "IC31") (pin "28") (pinfunction "PC5(ADC5/SCL)_28") (pintype "bidirectional"))
    )
    (net (code "64") (name "unconnected-(IC31-PD3(INT1)-Pad1)") (class "Default")
      (node (ref "IC31") (pin "1") (pinfunction "PD3(INT1)_1") (pintype "bidirectional"))
    )
    (net (code "65") (name "unconnected-(IC31-PD5(T1)-Pad9)") (class "Default")
      (node (ref "IC31") (pin "9") (pinfunction "PD5(T1)_9") (pintype "bidirectional"))
    )
    (net (code "66") (name "unconnected-(IC31-PD6(AIN0)-Pad10)") (class "Default")
      (node (ref "IC31") (pin "10") (pinfunction "PD6(AIN0)_10") (pintype "bidirectional"))
    )
    (net (code "67") (name "unconnected-(IC31-PD7(AIN1)-Pad11)") (class "Default")
      (node (ref "IC31") (pin "11") (pinfunction "PD7(AIN1)_11") (pintype "bidirectional"))
    )
    (net (code "68") (name "unconnected-(U$4-23{slash}USB_DP-Pad12)") (class "Default")
      (node (ref "U$4") (pin "12") (pinfunction "23/USB_DP_12") (pintype "bidirectional"))
    )
    (net (code "69") (name "unconnected-(U$4-24{slash}USB_DM-Pad13)") (class "Default")
      (node (ref "U$4") (pin "13") (pinfunction "24/USB_DM_13") (pintype "bidirectional"))
    )
    (net (code "70") (name "unconnected-(U$4-BUT-Pad3)") (class "Default")
      (node (ref "U$4") (pin "3") (pinfunction "BUT_3") (pintype "bidirectional"))
    )
    (net (code "71") (name "unconnected-(U$4-VBAT-Pad38)") (class "Default")
      (node (ref "U$4") (pin "38") (pinfunction "VBAT_38") (pintype "bidirectional"))
    )
  )
)
